# HZSneckV1_2.net
KiCad netlist of a schematic drawn in Altium Designer
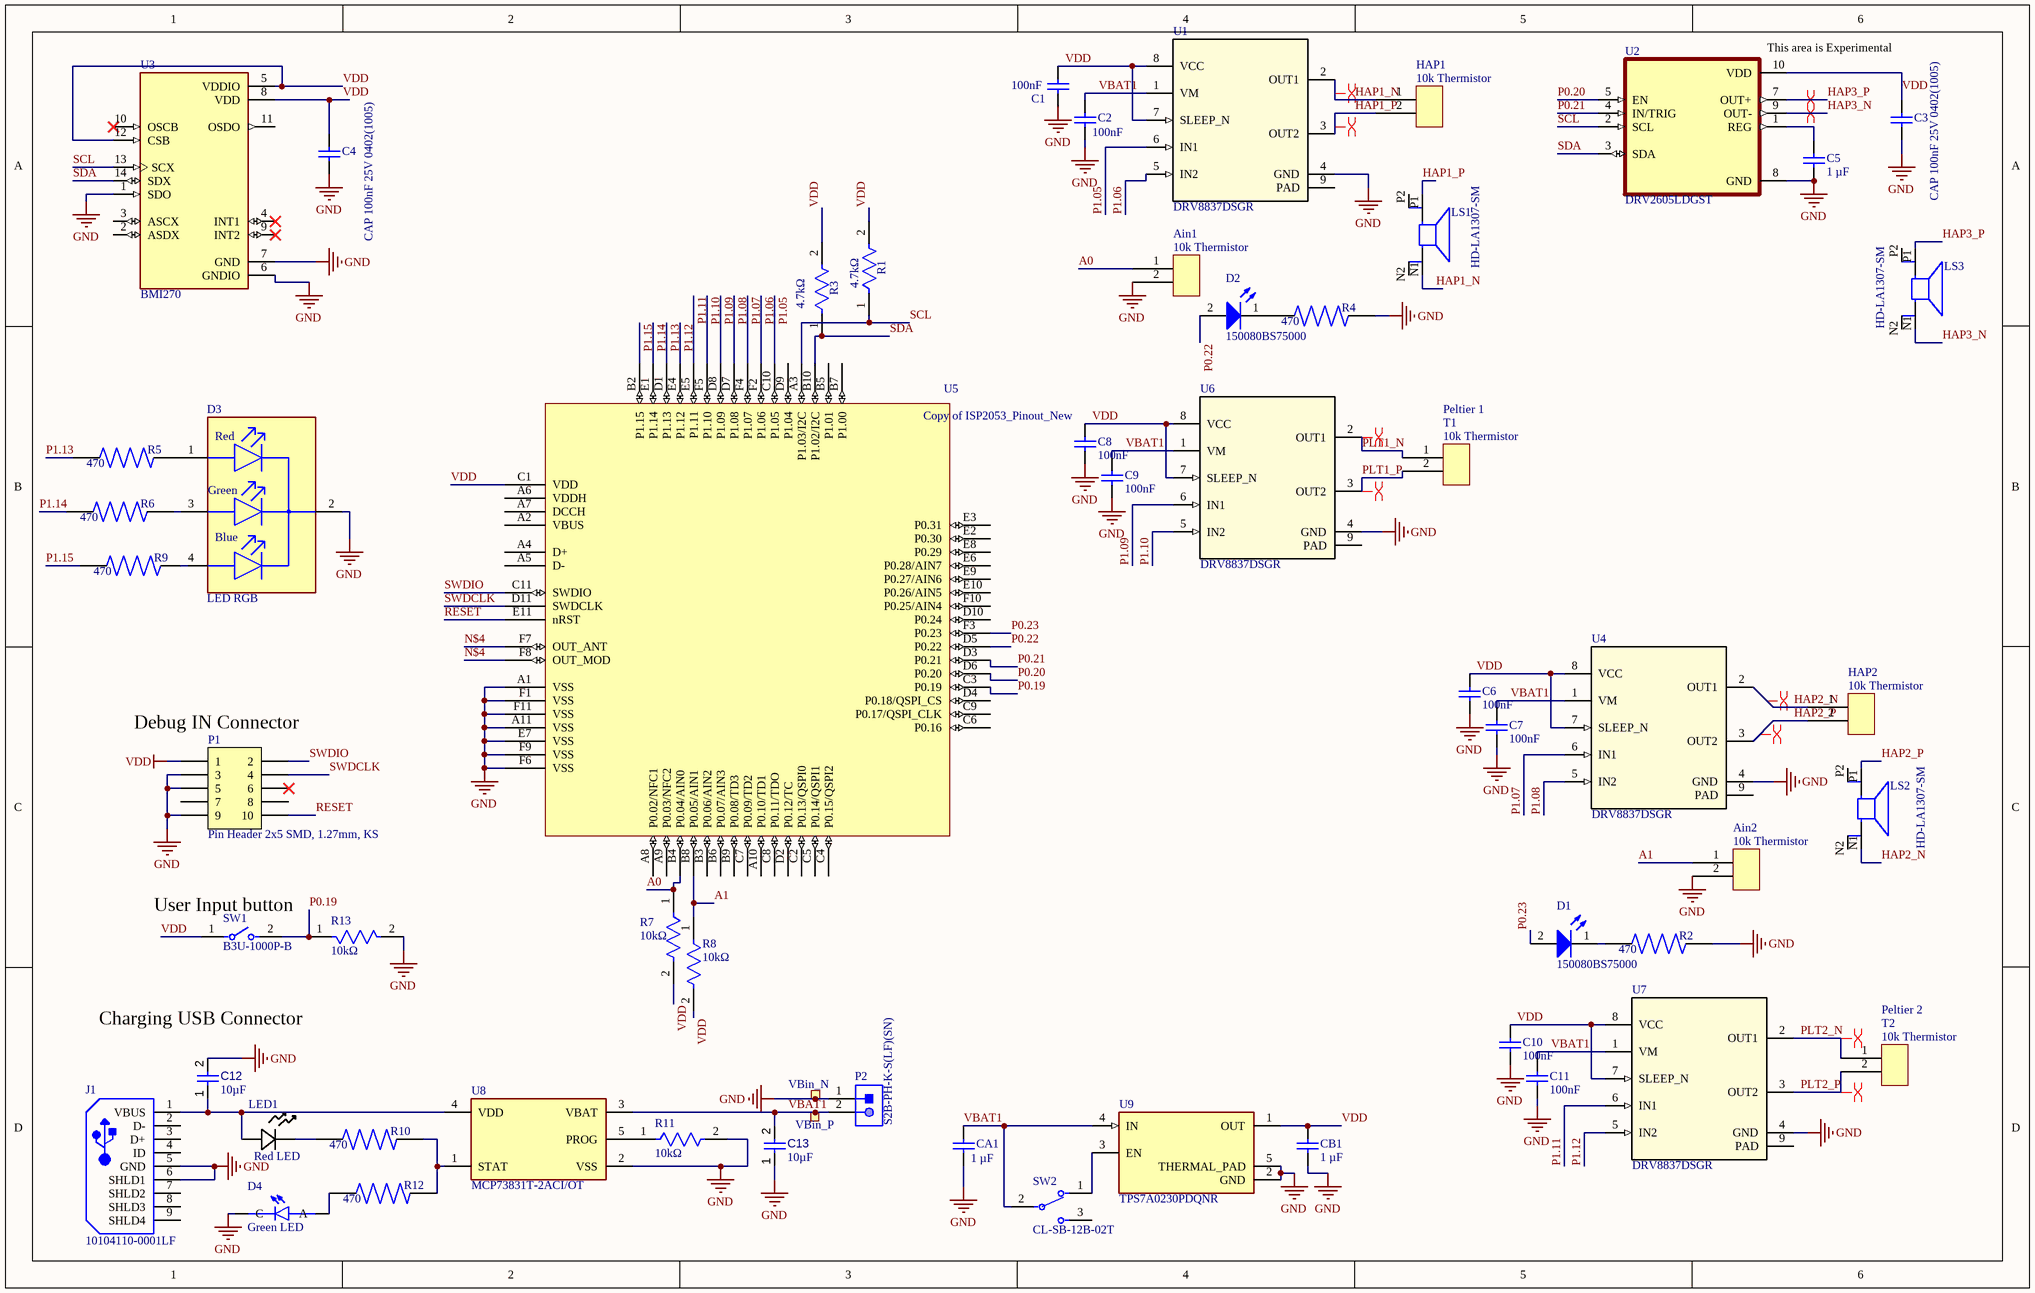
[diagram p0: HZSneckV1.2.SchDoc]

(export (version "E")
  (design (tool "Eeschema 10.0.6"))
  (components
    (comp (ref "Ain1")
      (value "10k Thermistor Custom")
      (footprint "10k Thermistor Pad")
      (description "Custom Pad for the Thermistor")
      (libsource (lib "Georgia Institute of Technology") (part "HPcustomPad-10k Thermistor"))
    )
    (comp (ref "Ain2")
      (value "10k Thermistor Custom")
      (footprint "10k Thermistor Pad")
      (description "Custom Pad for the Thermistor")
      (libsource (lib "Georgia Institute of Technology") (part "HPcustomPad-10k Thermistor"))
    )
    (comp (ref "C1")
      (value "100nF")
      (footprint "CAPC0402(1005)60_L")
      (description "CAP 100nF 25V ±20% 0402 (1005 Metric) Thickness 0.6mm SMD")
      (fields (field (name "TOLERANCE") "Â±20%"))
      (libsource (lib "Altium Content Vault") (part "CAP"))
    )
    (comp (ref "C2")
      (value "100nF")
      (footprint "CAPC0402(1005)60_L")
      (description "CAP 100nF 25V ±20% 0402 (1005 Metric) Thickness 0.6mm SMD")
      (fields (field (name "TOLERANCE") "Â±20%"))
      (libsource (lib "Altium Content Vault") (part "CAP"))
    )
    (comp (ref "C3")
      (value "CAP 100nF 25V 0402(1005)")
      (footprint "CAPC0402(1005)60_L")
      (description "CAP 100nF 25V ±20% 0402 (1005 Metric) Thickness 0.6mm SMD")
      (fields (field (name "TOLERANCE") "Â±20%"))
      (libsource (lib "Altium Content Vault") (part "CAP"))
    )
    (comp (ref "C4")
      (value "CAP 100nF 25V 0402(1005)")
      (footprint "CAPC0402(1005)60_L")
      (description "CAP 100nF 25V ±20% 0402 (1005 Metric) Thickness 0.6mm SMD")
      (fields (field (name "TOLERANCE") "Â±20%"))
      (libsource (lib "Altium Content Vault") (part "CAP"))
    )
    (comp (ref "C5")
      (value "1 µF")
      (footprint "CAPC1005X56X25ML10T15")
      (description "1 µF ±10% 6.3V Ceramic Capacitor X5R 0402 (1005 Metric)\r\n04026D105KAT4A")
      (fields
        (field (name "PART NUMBER") "04026D105KAT4A")
        (field (name "MANUFACTURER") "AVX Interconnect / Elco")
      )
      (libsource (lib "Altium Content Vault") (part "CAP"))
    )
    (comp (ref "C6")
      (value "100nF")
      (footprint "CAPC0402(1005)60_L")
      (description "CAP 100nF 25V ±20% 0402 (1005 Metric) Thickness 0.6mm SMD")
      (fields (field (name "TOLERANCE") "Â±20%"))
      (libsource (lib "Altium Content Vault") (part "CAP"))
    )
    (comp (ref "C7")
      (value "100nF")
      (footprint "CAPC0402(1005)60_L")
      (description "CAP 100nF 25V ±20% 0402 (1005 Metric) Thickness 0.6mm SMD")
      (fields (field (name "TOLERANCE") "Â±20%"))
      (libsource (lib "Altium Content Vault") (part "CAP"))
    )
    (comp (ref "C8")
      (value "100nF")
      (footprint "CAPC0402(1005)60_L")
      (description "CAP 100nF 25V ±20% 0402 (1005 Metric) Thickness 0.6mm SMD")
      (fields (field (name "TOLERANCE") "Â±20%"))
      (libsource (lib "Altium Content Vault") (part "CAP"))
    )
    (comp (ref "C9")
      (value "100nF")
      (footprint "CAPC0402(1005)60_L")
      (description "CAP 100nF 25V ±20% 0402 (1005 Metric) Thickness 0.6mm SMD")
      (fields (field (name "TOLERANCE") "Â±20%"))
      (libsource (lib "Altium Content Vault") (part "CAP"))
    )
    (comp (ref "C10")
      (value "100nF")
      (footprint "CAPC0402(1005)60_L")
      (description "CAP 100nF 25V ±20% 0402 (1005 Metric) Thickness 0.6mm SMD")
      (fields (field (name "TOLERANCE") "Â±20%"))
      (libsource (lib "Altium Content Vault") (part "CAP"))
    )
    (comp (ref "C11")
      (value "100nF")
      (footprint "CAPC0402(1005)60_L")
      (description "CAP 100nF 25V ±20% 0402 (1005 Metric) Thickness 0.6mm SMD")
      (fields (field (name "TOLERANCE") "Â±20%"))
      (libsource (lib "Altium Content Vault") (part "CAP"))
    )
    (comp (ref "C12")
      (value "10µF")
      (footprint "CAPC0402(1005)60_L")
      (description "Chip Capacitor, 10µF +/-40%, 6.3V, 0402, Thickness 0.6 mm")
      (fields (field (name "TOLERANCE") "10%") (field (name "Comment") "Capacitor 10µF +/-40% 6.3V 0402"))
      (libsource (lib "Georgia Institute of Technology") (part "CAP-NP-2"))
    )
    (comp (ref "C13")
      (value "10µF")
      (footprint "CAPC0402(1005)60_L")
      (description "Chip Capacitor, 10µF +/-40%, 6.3V, 0402, Thickness 0.6 mm")
      (fields (field (name "TOLERANCE") "10%") (field (name "Comment") "Capacitor 10µF +/-40% 6.3V 0402"))
      (libsource (lib "Georgia Institute of Technology") (part "CAP-NP-2"))
    )
    (comp (ref "CA1")
      (value "1 µF")
      (footprint "CAPC1005X56X25ML10T15")
      (description "1 µF ±10% 6.3V Ceramic Capacitor X5R 0402 (1005 Metric)\r\n04026D105KAT4A")
      (fields
        (field (name "PART NUMBER") "04026D105KAT4A")
        (field (name "MANUFACTURER") "AVX Interconnect / Elco")
      )
      (libsource (lib "Altium Content Vault") (part "CAP"))
    )
    (comp (ref "CB1")
      (value "1 µF")
      (footprint "CAPC1005X56X25ML10T15")
      (description "1 µF ±10% 6.3V Ceramic Capacitor X5R 0402 (1005 Metric)\r\n04026D105KAT4A")
      (fields
        (field (name "PART NUMBER") "04026D105KAT4A")
        (field (name "MANUFACTURER") "AVX Interconnect / Elco")
      )
      (libsource (lib "Altium Content Vault") (part "CAP"))
    )
    (comp (ref "D1")
      (value "150080BS75000")
      (footprint "WL-SMCW_0805_150080xx75000")
      (description "Led, Blue, 470 Nm, 3.2 V, 30 Ma, 145 Mcd Rohs Compliant: Yes")
      (libsource (lib "Altium Content Vault") (part "LED_Blue_2A-1K"))
    )
    (comp (ref "D2")
      (value "150080BS75000")
      (footprint "WL-SMCW_0805_150080xx75000")
      (description "Led, Blue, 470 Nm, 3.2 V, 30 Ma, 145 Mcd Rohs Compliant: Yes")
      (libsource (lib "Altium Content Vault") (part "LED_Blue_2A-1K"))
    )
    (comp (ref "D3")
      (value "LED RGB")
      (footprint "FP-AAA3528LSEKJ3ZGKQBKS-MFG")
      (description "LED RGB CLEAR 4SMD\r\nAAA3528LSEKJ3ZGKQBKS")
      (libsource (lib "Altium Content Vault") (part "443e5383a7a0c9f1439af3e1184479d"))
    )
    (comp (ref "D4")
      (value "Green LED")
      (footprint "LEDC2012X120N")
      (description "Green LED, 565 nm 0805Diffused, Rectangle Lens SMD package\r\nSML-LXT0805GW-TR")
      (fields (field (name "MF") "Lumex Opto/Components") (field (name "MP") "SML-LXT0805GW-TR"))
      (libsource (lib "Georgia Institute of Technology") (part "SML-LXT0805GW-TR"))
    )
    (comp (ref "HAP1")
      (value "10k Thermistor Custom")
      (footprint "10k Thermistor Pad")
      (description "Custom Pad for the Thermistor")
      (libsource (lib "Georgia Institute of Technology") (part "HPcustomPad-10k Thermistor"))
    )
    (comp (ref "HAP2")
      (value "10k Thermistor Custom")
      (footprint "10k Thermistor Pad")
      (description "Custom Pad for the Thermistor")
      (libsource (lib "Georgia Institute of Technology") (part "HPcustomPad-10k Thermistor"))
    )
    (comp (ref "J1")
      (value "10104110-0001LF")
      (footprint "FCI-10104110-0001LF_V")
      (description "Micro USB, Receptacle, -55 to 85 degC, 5-Pin SMD, RoHS, Tape and Reel")
      (fields (field (name "MANUFACTURER") "FCI Electronics"))
      (libsource (lib "Altium Content Vault") (part "USB-5-4SHLD"))
    )
    (comp (ref "LED1")
      (value "Red LED")
      (footprint "LED_LS R976_AOS")
      (description "LS R976-NR-1")
      (fields (field (name "COPYRIGHT") "Copyright (C) 2025 Ultra Librarian. All rights reserved."))
      (libsource (lib "Georgia Institute of Technology") (part "LS R976-NR-1"))
    )
    (comp (ref "LS1")
      (value "HD-LA1307-SM")
      (footprint "XDCR_HD-LA1307-SM")
      (description "13X13MM LRA HAPTIC 154HZ")
      (fields (field (name "MF") "PUI Audio, Inc."))
      (libsource (lib "Georgia Institute of Technology") (part "HD-LA1307-SM"))
    )
    (comp (ref "LS2")
      (value "HD-LA1307-SM")
      (footprint "XDCR_HD-LA1307-SM")
      (description "13X13MM LRA HAPTIC 154HZ")
      (fields (field (name "MF") "PUI Audio, Inc."))
      (libsource (lib "Georgia Institute of Technology") (part "HD-LA1307-SM"))
    )
    (comp (ref "LS3")
      (value "HD-LA1307-SM")
      (footprint "XDCR_HD-LA1307-SM")
      (description "13X13MM LRA HAPTIC 154HZ")
      (fields (field (name "MF") "PUI Audio, Inc."))
      (libsource (lib "Georgia Institute of Technology") (part "HD-LA1307-SM"))
    )
    (comp (ref "P1")
      (value "Pin Header 2x5 SMD, 1.27mm, KS")
      (footprint "HDR_2x5-SMD-1.27mm-K")
      (description "Pin Header 2x5, 1.27mm (50mil), SMD, Keying Shroud")
      (fields
        (field (name "MANUFACTURER PART NUMBER") "3132-10MS0BK00R1")
        (field (name "MANUFACTURER") "W-CON")
        (field (name "PUBLISHER") "Nordic Semiconductor")
      )
      (libsource (lib "Georgia Institute of Technology") (part "Pin Header 2x5 SMD, 1.27mm, KS"))
    )
    (comp (ref "P2")
      (value "S2B-PH-K-S(LF)(SN)")
      (footprint "JST-S2B-PH-K-S_V")
      (fields (field (name "TOLERANCE") "20%"))
      (libsource (lib "Altium Content Vault") (part "CN-1P-M-R2"))
    )
    (comp (ref "R1")
      (value "4.7kΩ")
      (footprint "FP-TFCR0603-MFG")
      (description "RES Thin Film,  4.7kΩ, 1%, 0.1W, 50ppm/°C, 0603TFCR0603-10W-C-4701FT-1K")
      (libsource (lib "Altium Content Vault") (part "1029c3af85768c4190bb7ad29bc67b5"))
    )
    (comp (ref "R2")
      (value "470")
      (footprint "RESC1608X55N")
      (description "RESISTOR, SURGE, 470 OHM 1% 0603")
      (fields (field (name "MP") "SG73P1JTTD4700F"))
      (libsource (lib "Georgia Institute of Technology") (part "SG73P1JTTD4700F"))
    )
    (comp (ref "R3")
      (value "4.7kΩ")
      (footprint "FP-TFCR0603-MFG")
      (description "RES Thin Film,  4.7kΩ, 1%, 0.1W, 50ppm/°C, 0603TFCR0603-10W-C-4701FT-1K")
      (libsource (lib "Altium Content Vault") (part "1029c3af85768c4190bb7ad29bc67b5"))
    )
    (comp (ref "R4")
      (value "470")
      (footprint "RESC1608X55N")
      (description "RESISTOR, SURGE, 470 OHM 1% 0603")
      (fields (field (name "MP") "SG73P1JTTD4700F"))
      (libsource (lib "Georgia Institute of Technology") (part "SG73P1JTTD4700F"))
    )
    (comp (ref "R5")
      (value "470")
      (footprint "RESC1608X55N")
      (description "RESISTOR, SURGE, 470 OHM 1% 0603")
      (fields (field (name "MP") "SG73P1JTTD4700F"))
      (libsource (lib "Georgia Institute of Technology") (part "SG73P1JTTD4700F"))
    )
    (comp (ref "R6")
      (value "470")
      (footprint "RESC1608X55N")
      (description "RESISTOR, SURGE, 470 OHM 1% 0603")
      (fields (field (name "MP") "SG73P1JTTD4700F"))
      (libsource (lib "Georgia Institute of Technology") (part "SG73P1JTTD4700F"))
    )
    (comp (ref "R7")
      (value "10kΩ")
      (footprint "FP-AC0603-IPC_A")
      (description "RES 10kΩ 5.00% 0.2W 0603\r\nAC0603JR-7W10KL")
      (libsource (lib "Altium Content Vault") (part "1029c3af85768c4190bb7ad29bc67b5"))
    )
    (comp (ref "R8")
      (value "10kΩ")
      (footprint "FP-AC0603-IPC_A")
      (description "RES 10kΩ 5.00% 0.2W 0603\r\nAC0603JR-7W10KL")
      (libsource (lib "Altium Content Vault") (part "1029c3af85768c4190bb7ad29bc67b5"))
    )
    (comp (ref "R9")
      (value "470")
      (footprint "RESC1608X55N")
      (description "RESISTOR, SURGE, 470 OHM 1% 0603")
      (fields (field (name "MP") "SG73P1JTTD4700F"))
      (libsource (lib "Georgia Institute of Technology") (part "SG73P1JTTD4700F"))
    )
    (comp (ref "R10")
      (value "470")
      (footprint "RESC1608X55N")
      (description "RESISTOR, SURGE, 470 OHM 1% 0603")
      (fields (field (name "MP") "SG73P1JTTD4700F"))
      (libsource (lib "Georgia Institute of Technology") (part "SG73P1JTTD4700F"))
    )
    (comp (ref "R11")
      (value "10kΩ")
      (footprint "FP-AC0603-IPC_A")
      (description "RES 10kΩ 5.00% 0.2W 0603\r\nAC0603JR-7W10KL")
      (libsource (lib "Altium Content Vault") (part "1029c3af85768c4190bb7ad29bc67b5"))
    )
    (comp (ref "R12")
      (value "470")
      (footprint "RESC1608X55N")
      (description "RESISTOR, SURGE, 470 OHM 1% 0603")
      (fields (field (name "MP") "SG73P1JTTD4700F"))
      (libsource (lib "Georgia Institute of Technology") (part "SG73P1JTTD4700F"))
    )
    (comp (ref "R13")
      (value "10kΩ")
      (footprint "FP-AC0603-IPC_A")
      (description "RES 10kΩ 5.00% 0.2W 0603\r\nAC0603JR-7W10KL")
      (libsource (lib "Altium Content Vault") (part "1029c3af85768c4190bb7ad29bc67b5"))
    )
    (comp (ref "SW1")
      (value "B3U-1000P-B")
      (footprint "FP-B3U-1000P-B-MFG")
      (description "SWITCH TACTILE SPST-NO 0.05A 12V")
      (fields
        (field (name "OCTOPART") "https://octopart.com/b3u-1000p-b-omron-1057356")
        (field (name "MANUFACTURER") "Omron")
      )
      (libsource (lib "Altium Content Vault") (part "bb27bde45df87f1f469753f287ef5ae"))
    )
    (comp (ref "SW2")
      (value "CL-SB-12B-02T")
      (footprint "FP-CL-SB-12B-02T-MFG")
      (description "SWITCH SLIDE SPDT 200MA 12V")
      (libsource (lib "Altium Content Vault") (part "39e195cbbadc85d1df0d7eb6847d379"))
    )
    (comp (ref "T1")
      (value "Peltier 1")
      (footprint "10k Thermistor Pad")
      (description "Custom Pad for the Thermistor")
      (libsource (lib "Georgia Institute of Technology") (part "HPcustomPad-10k Thermistor"))
    )
    (comp (ref "T2")
      (value "Peltier 2")
      (footprint "10k Thermistor Pad")
      (description "Custom Pad for the Thermistor")
      (libsource (lib "Georgia Institute of Technology") (part "HPcustomPad-10k Thermistor"))
    )
    (comp (ref "U1")
      (value "DRV8837DSGR")
      (footprint "DSG0008A")
      (description "12-V, 1.8-A H-bridge motor driver 8-WSON -40 to 85")
      (fields (field (name "COPYRIGHT") "Copyright (C) 2025 Ultra Librarian. All rights reserved."))
      (libsource (lib "Georgia Institute of Technology") (part "DRV8837DSGR"))
    )
    (comp (ref "U2")
      (value "DRV2605LDGST")
      (footprint "SOP50P490X110-10N")
      (description "Haptic driver for ERM/LRA with 2-V operation, waveform library & auto-resonance tracking")
      (fields (field (name "MF") "Texas Instruments"))
      (libsource (lib "Georgia Institute of Technology") (part "DRV2605LDGST"))
    )
    (comp (ref "U3")
      (value "BMI270")
      (footprint "XDCR_BMI270")
      (description "Accelerometer, Gyroscope, 6 Axis Sensor IÂ²C, SPI Output")
      (fields (field (name "MF") "Bosch Sensortec") (field (name "DIGI-KEY_PART_NUMBER") "828-1091-2-ND"))
      (libsource (lib "Georgia Institute of Technology") (part "BMI270"))
    )
    (comp (ref "U4")
      (value "DRV8837DSGR")
      (footprint "DSG0008A")
      (description "12-V, 1.8-A H-bridge motor driver 8-WSON -40 to 85")
      (fields (field (name "COPYRIGHT") "Copyright (C) 2025 Ultra Librarian. All rights reserved."))
      (libsource (lib "Georgia Institute of Technology") (part "DRV8837DSGR"))
    )
    (comp (ref "U5")
      (value "Copy of ISP2053_Pinout_New")
      (footprint "Copy of ISP2053-AX")
      (description "ISP Smart Bluetooth Module")
      (fields (field (name "ISP_PART") "ISP1807") (field (name "SOURCE") "ISPlibSch.SchLib"))
      (libsource (lib "Georgia Institute of Technology") (part "ISP2053_Pinout_New"))
    )
    (comp (ref "U6")
      (value "DRV8837DSGR")
      (footprint "DSG0008A")
      (description "12-V, 1.8-A H-bridge motor driver 8-WSON -40 to 85")
      (fields (field (name "COPYRIGHT") "Copyright (C) 2025 Ultra Librarian. All rights reserved."))
      (libsource (lib "Georgia Institute of Technology") (part "DRV8837DSGR"))
    )
    (comp (ref "U7")
      (value "DRV8837DSGR")
      (footprint "DSG0008A")
      (description "12-V, 1.8-A H-bridge motor driver 8-WSON -40 to 85")
      (fields (field (name "COPYRIGHT") "Copyright (C) 2025 Ultra Librarian. All rights reserved."))
      (libsource (lib "Georgia Institute of Technology") (part "DRV8837DSGR"))
    )
    (comp (ref "U8")
      (value "MCP73831T-2ACI/OT")
      (footprint "FP-C04-091-OT-IPC_B")
      (description "IC CONTROLLR LI-ION 4.2V SOT23-5")
      (libsource (lib "Altium Content Vault") (part "61f5a3bb3429d9e0caadea342aa3b19"))
    )
    (comp (ref "U9")
      (value "TPS7A0230PDQNR")
      (footprint "IC_TPS7A0230PDQNR")
      (description "200-mA, nanopower-IQ (25 nA), low-dropout (LDO) voltage regulator with enable")
      (fields (field (name "MF") "Texas Instruments"))
      (libsource (lib "Georgia Institute of Technology") (part "TPS7A0230PDQNR"))
    )
    (comp (ref "VBin_N")
      (value "TP_SMD_Ø1.0MM")
      (footprint "TP_SMD_Ø1.0mm")
      (description "1.0mm circular SMD testpad")
      (fields
        (field (name "MANUFACTURER") "Nordic Semiconductor")
        (field (name "MANUFACTURER PART NUMBER") "N.A.")
        (field (name "PUBLISHER") "Nordic Semiconductor")
      )
      (libsource (lib "") (part "TP_SMD_Ø1.5MM_1"))
    )
    (comp (ref "VBin_P")
      (value "TP_SMD_Ø1.0MM")
      (footprint "TP_SMD_Ø1.0mm")
      (description "1.0mm circular SMD testpad")
      (fields
        (field (name "MANUFACTURER") "Nordic Semiconductor")
        (field (name "MANUFACTURER PART NUMBER") "N.A.")
        (field (name "PUBLISHER") "Nordic Semiconductor")
      )
      (libsource (lib "Georgia Institute of Technology") (part "TP_SMD_Ø1.5MM"))
    )
  )
  (nets
    (net (code "2") (name "/A0") (class "Default")
      (node (ref "Ain1") (pin "1") (pintype "passive"))
      (node (ref "R7") (pin "1") (pinfunction "1_1") (pintype "passive"))
      (node (ref "U5") (pin "B4") (pinfunction "P0.04/AIN0_B4") (pintype "bidirectional"))
    )
    (net (code "3") (name "/A1") (class "Default")
      (node (ref "Ain2") (pin "1") (pintype "passive"))
      (node (ref "R8") (pin "1") (pinfunction "1_1") (pintype "passive"))
      (node (ref "U5") (pin "B8") (pinfunction "P0.05/AIN1_B8") (pintype "bidirectional"))
    )
    (net (code "4") (name "/HAP1_N") (class "Default")
      (node (ref "HAP1") (pin "1") (pintype "passive"))
      (node (ref "LS1") (pin "N1") (pinfunction "N1_N1") (pintype "passive"))
      (node (ref "U1") (pin "2") (pinfunction "OUT1_2") (pintype "power_in"))
    )
    (net (code "5") (name "/HAP1_P") (class "Default")
      (node (ref "HAP1") (pin "2") (pintype "passive"))
      (node (ref "LS1") (pin "P1") (pinfunction "P1_P1") (pintype "passive"))
      (node (ref "U1") (pin "3") (pinfunction "OUT2_3") (pintype "power_in"))
    )
    (net (code "6") (name "/HAP2_N") (class "Default")
      (node (ref "HAP2") (pin "1") (pintype "passive"))
      (node (ref "LS2") (pin "N1") (pinfunction "N1_N1") (pintype "passive"))
      (node (ref "U4") (pin "2") (pinfunction "OUT1_2") (pintype "power_in"))
    )
    (net (code "7") (name "/HAP2_P") (class "Default")
      (node (ref "HAP2") (pin "2") (pintype "passive"))
      (node (ref "LS2") (pin "P1") (pinfunction "P1_P1") (pintype "passive"))
      (node (ref "U4") (pin "3") (pinfunction "OUT2_3") (pintype "power_in"))
    )
    (net (code "8") (name "/HAP3_N") (class "Default")
      (node (ref "LS3") (pin "N1") (pinfunction "N1_N1") (pintype "passive"))
      (node (ref "U2") (pin "9") (pinfunction "OUT-_9") (pintype "output"))
    )
    (net (code "9") (name "/HAP3_P") (class "Default")
      (node (ref "LS3") (pin "P1") (pinfunction "P1_P1") (pintype "passive"))
      (node (ref "U2") (pin "7") (pinfunction "OUT+_7") (pintype "output"))
    )
    (net (code "10") (name "/N$4") (class "Default")
      (node (ref "U5") (pin "F7") (pinfunction "OUT_ANT_F7") (pintype "bidirectional"))
      (node (ref "U5") (pin "F8") (pinfunction "OUT_MOD_F8") (pintype "bidirectional"))
    )
    (net (code "11") (name "/P0.19") (class "Default")
      (node (ref "R13") (pin "1") (pinfunction "1_1") (pintype "passive"))
      (node (ref "SW1") (pin "2") (pinfunction "2_2") (pintype "passive"))
      (node (ref "U5") (pin "C3") (pinfunction "P0.19_C3") (pintype "bidirectional"))
    )
    (net (code "12") (name "/P0.20") (class "Default")
      (node (ref "U2") (pin "5") (pinfunction "EN_5") (pintype "input"))
      (node (ref "U5") (pin "D6") (pinfunction "P0.20_D6") (pintype "bidirectional"))
    )
    (net (code "13") (name "/P0.21") (class "Default")
      (node (ref "U2") (pin "4") (pinfunction "IN/TRIG_4") (pintype "input"))
      (node (ref "U5") (pin "D3") (pinfunction "P0.21_D3") (pintype "bidirectional"))
    )
    (net (code "14") (name "/P0.22") (class "Default")
      (node (ref "D2") (pin "2") (pinfunction "A_2") (pintype "passive"))
      (node (ref "U5") (pin "D5") (pinfunction "P0.22_D5") (pintype "bidirectional"))
    )
    (net (code "15") (name "/P0.23") (class "Default")
      (node (ref "D1") (pin "2") (pinfunction "A_2") (pintype "passive"))
      (node (ref "U5") (pin "F3") (pinfunction "P0.23_F3") (pintype "bidirectional"))
    )
    (net (code "16") (name "/P1.05") (class "Default")
      (node (ref "U1") (pin "6") (pinfunction "IN1_6") (pintype "input"))
      (node (ref "U5") (pin "C10") (pinfunction "P1.05_C10") (pintype "bidirectional"))
    )
    (net (code "17") (name "/P1.06") (class "Default")
      (node (ref "U1") (pin "5") (pinfunction "IN2_5") (pintype "input"))
      (node (ref "U5") (pin "F2") (pinfunction "P1.06_F2") (pintype "bidirectional"))
    )
    (net (code "18") (name "/P1.07") (class "Default")
      (node (ref "U4") (pin "6") (pinfunction "IN1_6") (pintype "input"))
      (node (ref "U5") (pin "F4") (pinfunction "P1.07_F4") (pintype "bidirectional"))
    )
    (net (code "19") (name "/P1.08") (class "Default")
      (node (ref "U4") (pin "5") (pinfunction "IN2_5") (pintype "input"))
      (node (ref "U5") (pin "D7") (pinfunction "P1.08_D7") (pintype "bidirectional"))
    )
    (net (code "20") (name "/P1.09") (class "Default")
      (node (ref "U5") (pin "D8") (pinfunction "P1.09_D8") (pintype "bidirectional"))
      (node (ref "U6") (pin "6") (pinfunction "IN1_6") (pintype "input"))
    )
    (net (code "21") (name "/P1.10") (class "Default")
      (node (ref "U5") (pin "F5") (pinfunction "P1.10_F5") (pintype "bidirectional"))
      (node (ref "U6") (pin "5") (pinfunction "IN2_5") (pintype "input"))
    )
    (net (code "22") (name "/P1.11") (class "Default")
      (node (ref "U5") (pin "E5") (pinfunction "P1.11_E5") (pintype "bidirectional"))
      (node (ref "U7") (pin "6") (pinfunction "IN1_6") (pintype "input"))
    )
    (net (code "23") (name "/P1.12") (class "Default")
      (node (ref "U5") (pin "E4") (pinfunction "P1.12_E4") (pintype "bidirectional"))
      (node (ref "U7") (pin "5") (pinfunction "IN2_5") (pintype "input"))
    )
    (net (code "24") (name "/P1.13") (class "Default")
      (node (ref "R5") (pin "1") (pinfunction "1_1") (pintype "passive"))
      (node (ref "U5") (pin "D1") (pinfunction "P1.13_D1") (pintype "bidirectional"))
    )
    (net (code "25") (name "/P1.14") (class "Default")
      (node (ref "R6") (pin "1") (pinfunction "1_1") (pintype "passive"))
      (node (ref "U5") (pin "E1") (pinfunction "P1.14_E1") (pintype "bidirectional"))
    )
    (net (code "26") (name "/P1.15") (class "Default")
      (node (ref "R9") (pin "1") (pinfunction "1_1") (pintype "passive"))
      (node (ref "U5") (pin "B2") (pinfunction "P1.15_B2") (pintype "bidirectional"))
    )
    (net (code "27") (name "/PLT1_N") (class "Default")
      (node (ref "T1") (pin "1") (pintype "passive"))
      (node (ref "U6") (pin "2") (pinfunction "OUT1_2") (pintype "power_in"))
    )
    (net (code "28") (name "/PLT1_P") (class "Default")
      (node (ref "T1") (pin "2") (pintype "passive"))
      (node (ref "U6") (pin "3") (pinfunction "OUT2_3") (pintype "power_in"))
    )
    (net (code "29") (name "/PLT2_N") (class "Default")
      (node (ref "T2") (pin "1") (pintype "passive"))
      (node (ref "U7") (pin "2") (pinfunction "OUT1_2") (pintype "power_in"))
    )
    (net (code "30") (name "/PLT2_P") (class "Default")
      (node (ref "T2") (pin "2") (pintype "passive"))
      (node (ref "U7") (pin "3") (pinfunction "OUT2_3") (pintype "power_in"))
    )
    (net (code "31") (name "/RESET") (class "Default")
      (node (ref "P1") (pin "10") (pinfunction "10_10") (pintype "passive"))
      (node (ref "U5") (pin "E11") (pinfunction "nRST_E11") (pintype "power_in"))
    )
    (net (code "32") (name "/SCL") (class "Default")
      (node (ref "R1") (pin "1") (pinfunction "1_1") (pintype "passive"))
      (node (ref "U2") (pin "2") (pinfunction "SCL_2") (pintype "input"))
      (node (ref "U3") (pin "13") (pinfunction "SCX_13") (pintype "input"))
      (node (ref "U5") (pin "A3") (pinfunction "P1.03/I2C_A3") (pintype "bidirectional"))
    )
    (net (code "33") (name "/SDA") (class "Default")
      (node (ref "R3") (pin "1") (pinfunction "1_1") (pintype "passive"))
      (node (ref "U2") (pin "3") (pinfunction "SDA_3") (pintype "bidirectional"))
      (node (ref "U3") (pin "14") (pinfunction "SDX_14") (pintype "bidirectional"))
      (node (ref "U5") (pin "B10") (pinfunction "P1.02/I2C_B10") (pintype "bidirectional"))
    )
    (net (code "34") (name "/SWDCLK") (class "Default")
      (node (ref "P1") (pin "4") (pinfunction "4_4") (pintype "passive"))
      (node (ref "U5") (pin "D11") (pinfunction "SWDCLK_D11") (pintype "passive"))
    )
    (net (code "35") (name "/SWDIO") (class "Default")
      (node (ref "P1") (pin "2") (pinfunction "2_2") (pintype "passive"))
      (node (ref "U5") (pin "C11") (pinfunction "SWDIO_C11") (pintype "bidirectional"))
    )
    (net (code "36") (name "/VBAT1") (class "Default")
      (node (ref "C11") (pin "2") (pinfunction "2_2") (pintype "passive"))
      (node (ref "C13") (pin "2") (pinfunction "2_2") (pintype "passive"))
      (node (ref "C2") (pin "2") (pinfunction "2_2") (pintype "passive"))
      (node (ref "C7") (pin "2") (pinfunction "2_2") (pintype "passive"))
      (node (ref "C9") (pin "2") (pinfunction "2_2") (pintype "passive"))
      (node (ref "CA1") (pin "2") (pinfunction "2_2") (pintype "passive"))
      (node (ref "P2") (pin "2") (pinfunction "2_2") (pintype "passive"))
      (node (ref "SW2") (pin "2") (pinfunction "C_2") (pintype "passive"))
      (node (ref "U1") (pin "1") (pinfunction "VM_1") (pintype "power_in"))
      (node (ref "U4") (pin "1") (pinfunction "VM_1") (pintype "power_in"))
      (node (ref "U6") (pin "1") (pinfunction "VM_1") (pintype "power_in"))
      (node (ref "U7") (pin "1") (pinfunction "VM_1") (pintype "power_in"))
      (node (ref "U8") (pin "3") (pinfunction "VBAT_3") (pintype "power_in"))
      (node (ref "U9") (pin "4") (pinfunction "IN_4") (pintype "input"))
      (node (ref "VBin_P") (pin "1") (pinfunction "1_1") (pintype "passive"))
    )
    (net (code "37") (name "GND") (class "Default")
      (node (ref "Ain1") (pin "2") (pintype "passive"))
      (node (ref "Ain2") (pin "2") (pintype "passive"))
      (node (ref "C1") (pin "1") (pinfunction "1_1") (pintype "passive"))
      (node (ref "C10") (pin "1") (pinfunction "1_1") (pintype "passive"))
      (node (ref "C11") (pin "1") (pinfunction "1_1") (pintype "passive"))
      (node (ref "C12") (pin "2") (pinfunction "2_2") (pintype "passive"))
      (node (ref "C13") (pin "1") (pinfunction "1_1") (pintype "passive"))
      (node (ref "C2") (pin "1") (pinfunction "1_1") (pintype "passive"))
      (node (ref "C3") (pin "1") (pinfunction "1_1") (pintype "passive"))
      (node (ref "C4") (pin "1") (pinfunction "1_1") (pintype "passive"))
      (node (ref "C5") (pin "1") (pinfunction "1_1") (pintype "passive"))
      (node (ref "C6") (pin "1") (pinfunction "1_1") (pintype "passive"))
      (node (ref "C7") (pin "1") (pinfunction "1_1") (pintype "passive"))
      (node (ref "C8") (pin "1") (pinfunction "1_1") (pintype "passive"))
      (node (ref "C9") (pin "1") (pinfunction "1_1") (pintype "passive"))
      (node (ref "CA1") (pin "1") (pinfunction "1_1") (pintype "passive"))
      (node (ref "CB1") (pin "1") (pinfunction "1_1") (pintype "passive"))
      (node (ref "D3") (pin "2") (pinfunction "COMMON_CATHODE_2") (pintype "passive"))
      (node (ref "D4") (pin "C") (pinfunction "C_C") (pintype "passive"))
      (node (ref "J1") (pin "5") (pinfunction "GND_5") (pintype "power_in"))
      (node (ref "J1") (pin "6") (pinfunction "SHLD1_6") (pintype "passive"))
      (node (ref "P1") (pin "3") (pinfunction "3_3") (pintype "passive"))
      (node (ref "P1") (pin "5") (pinfunction "5_5") (pintype "passive"))
      (node (ref "P1") (pin "9") (pinfunction "9_9") (pintype "passive"))
      (node (ref "P2") (pin "1") (pinfunction "1_1") (pintype "passive"))
      (node (ref "R11") (pin "2") (pinfunction "2_2") (pintype "passive"))
      (node (ref "R13") (pin "2") (pinfunction "2_2") (pintype "passive"))
      (node (ref "R2") (pin "2") (pinfunction "2_2") (pintype "passive"))
      (node (ref "R4") (pin "2") (pinfunction "2_2") (pintype "passive"))
      (node (ref "U1") (pin "4") (pinfunction "GND_4") (pintype "power_in"))
      (node (ref "U2") (pin "8") (pinfunction "GND_8") (pintype "power_in"))
      (node (ref "U3") (pin "1") (pinfunction "SDO_1") (pintype "input"))
      (node (ref "U3") (pin "6") (pinfunction "GNDIO_6") (pintype "power_in"))
      (node (ref "U3") (pin "7") (pinfunction "GND_7") (pintype "power_in"))
      (node (ref "U4") (pin "4") (pinfunction "GND_4") (pintype "power_in"))
      (node (ref "U5") (pin "A1") (pinfunction "VSS_A1") (pintype "power_in"))
      (node (ref "U5") (pin "A11") (pinfunction "VSS_A11") (pintype "power_in"))
      (node (ref "U5") (pin "E7") (pinfunction "VSS_E7") (pintype "power_in"))
      (node (ref "U5") (pin "F1") (pinfunction "VSS_F1") (pintype "power_in"))
      (node (ref "U5") (pin "F11") (pinfunction "VSS_F11") (pintype "power_in"))
      (node (ref "U5") (pin "F6") (pinfunction "VSS_F6") (pintype "power_in"))
      (node (ref "U5") (pin "F9") (pinfunction "VSS_F9") (pintype "power_in"))
      (node (ref "U6") (pin "4") (pinfunction "GND_4") (pintype "power_in"))
      (node (ref "U7") (pin "4") (pinfunction "GND_4") (pintype "power_in"))
      (node (ref "U8") (pin "2") (pinfunction "VSS_2") (pintype "power_in"))
      (node (ref "U9") (pin "2") (pinfunction "GND_2") (pintype "power_in"))
      (node (ref "U9") (pin "5") (pinfunction "THERMAL_PAD_5") (pintype "power_in"))
      (node (ref "VBin_N") (pin "1") (pinfunction "1_1") (pintype "passive"))
    )
    (net (code "38") (name "Net-(D1-K)") (class "Default")
      (node (ref "D1") (pin "1") (pinfunction "K_1") (pintype "passive"))
      (node (ref "R2") (pin "1") (pinfunction "1_1") (pintype "passive"))
    )
    (net (code "39") (name "Net-(D2-K)") (class "Default")
      (node (ref "D2") (pin "1") (pinfunction "K_1") (pintype "passive"))
      (node (ref "R4") (pin "1") (pinfunction "1_1") (pintype "passive"))
    )
    (net (code "40") (name "Net-(D3-ANODE_BLUE)") (class "Default")
      (node (ref "D3") (pin "4") (pinfunction "ANODE_BLUE_4") (pintype "passive"))
      (node (ref "R9") (pin "2") (pinfunction "2_2") (pintype "passive"))
    )
    (net (code "41") (name "Net-(D3-ANODE_GREEN)") (class "Default")
      (node (ref "D3") (pin "3") (pinfunction "ANODE_GREEN_3") (pintype "passive"))
      (node (ref "R6") (pin "2") (pinfunction "2_2") (pintype "passive"))
    )
    (net (code "42") (name "Net-(D3-ANODE_RED)") (class "Default")
      (node (ref "D3") (pin "1") (pinfunction "ANODE_RED_1") (pintype "passive"))
      (node (ref "R5") (pin "2") (pinfunction "2_2") (pintype "passive"))
    )
    (net (code "43") (name "Net-(D4-PadA)") (class "Default")
      (node (ref "D4") (pin "A") (pinfunction "A_A") (pintype "passive"))
      (node (ref "R12") (pin "1") (pinfunction "1_1") (pintype "passive"))
    )
    (net (code "44") (name "Net-(J1-VBUS)") (class "Default")
      (node (ref "C12") (pin "1") (pinfunction "1_1") (pintype "passive"))
      (node (ref "J1") (pin "1") (pinfunction "VBUS_1") (pintype "power_in"))
      (node (ref "LED1") (pin "2") (pinfunction "2_2") (pintype "passive"))
      (node (ref "U8") (pin "4") (pinfunction "VDD_4") (pintype "power_in"))
    )
    (net (code "45") (name "Net-(LED1-Pad1)") (class "Default")
      (node (ref "LED1") (pin "1") (pinfunction "1_1") (pintype "passive"))
      (node (ref "R10") (pin "1") (pinfunction "1_1") (pintype "passive"))
    )
    (net (code "46") (name "Net-(U2-REG)") (class "Default")
      (node (ref "C5") (pin "2") (pinfunction "2_2") (pintype "passive"))
      (node (ref "U2") (pin "1") (pinfunction "REG_1") (pintype "output"))
    )
    (net (code "47") (name "Net-(U8-PROG)") (class "Default")
      (node (ref "R11") (pin "1") (pinfunction "1_1") (pintype "passive"))
      (node (ref "U8") (pin "5") (pinfunction "PROG_5") (pintype "passive"))
    )
    (net (code "48") (name "Net-(U8-STAT)") (class "Default")
      (node (ref "R10") (pin "2") (pinfunction "2_2") (pintype "passive"))
      (node (ref "R12") (pin "2") (pinfunction "2_2") (pintype "passive"))
      (node (ref "U8") (pin "1") (pinfunction "STAT_1") (pintype "passive"))
    )
    (net (code "49") (name "Net-(U9-EN)") (class "Default")
      (node (ref "SW2") (pin "1") (pinfunction "1_1") (pintype "passive"))
      (node (ref "U9") (pin "3") (pinfunction "EN_3") (pintype "passive"))
    )
    (net (code "50") (name "VDD") (class "Default")
      (node (ref "C1") (pin "2") (pinfunction "2_2") (pintype "passive"))
      (node (ref "C10") (pin "2") (pinfunction "2_2") (pintype "passive"))
      (node (ref "C3") (pin "2") (pinfunction "2_2") (pintype "passive"))
      (node (ref "C4") (pin "2") (pinfunction "2_2") (pintype "passive"))
      (node (ref "C6") (pin "2") (pinfunction "2_2") (pintype "passive"))
      (node (ref "C8") (pin "2") (pinfunction "2_2") (pintype "passive"))
      (node (ref "CB1") (pin "2") (pinfunction "2_2") (pintype "passive"))
      (node (ref "P1") (pin "1") (pinfunction "1_1") (pintype "passive"))
      (node (ref "R1") (pin "2") (pinfunction "2_2") (pintype "passive"))
      (node (ref "R3") (pin "2") (pinfunction "2_2") (pintype "passive"))
      (node (ref "R7") (pin "2") (pinfunction "2_2") (pintype "passive"))
      (node (ref "R8") (pin "2") (pinfunction "2_2") (pintype "passive"))
      (node (ref "SW1") (pin "1") (pinfunction "1_1") (pintype "passive"))
      (node (ref "U1") (pin "7") (pinfunction "SLEEP_N_7") (pintype "input"))
      (node (ref "U1") (pin "8") (pinfunction "VCC_8") (pintype "power_in"))
      (node (ref "U2") (pin "10") (pinfunction "VDD_10") (pintype "power_in"))
      (node (ref "U3") (pin "12") (pinfunction "CSB_12") (pintype "input"))
      (node (ref "U3") (pin "5") (pinfunction "VDDIO_5") (pintype "power_in"))
      (node (ref "U3") (pin "8") (pinfunction "VDD_8") (pintype "power_in"))
      (node (ref "U4") (pin "7") (pinfunction "SLEEP_N_7") (pintype "input"))
      (node (ref "U4") (pin "8") (pinfunction "VCC_8") (pintype "power_in"))
      (node (ref "U5") (pin "C1") (pinfunction "VDD_C1") (pintype "power_in"))
      (node (ref "U6") (pin "7") (pinfunction "SLEEP_N_7") (pintype "input"))
      (node (ref "U6") (pin "8") (pinfunction "VCC_8") (pintype "power_in"))
      (node (ref "U7") (pin "7") (pinfunction "SLEEP_N_7") (pintype "input"))
      (node (ref "U7") (pin "8") (pinfunction "VCC_8") (pintype "power_in"))
      (node (ref "U9") (pin "1") (pinfunction "OUT_1") (pintype "power_in"))
    )
    (net (code "51") (name "unconnected-(J1-D+-Pad3)") (class "Default")
      (node (ref "J1") (pin "3") (pinfunction "D+_3") (pintype "passive"))
    )
    (net (code "52") (name "unconnected-(J1-D--Pad2)") (class "Default")
      (node (ref "J1") (pin "2") (pinfunction "D-_2") (pintype "passive"))
    )
    (net (code "53") (name "unconnected-(J1-ID-Pad4)") (class "Default")
      (node (ref "J1") (pin "4") (pinfunction "ID_4") (pintype "passive"))
    )
    (net (code "54") (name "unconnected-(J1-SHLD2-Pad7)") (class "Default")
      (node (ref "J1") (pin "7") (pinfunction "SHLD2_7") (pintype "passive"))
    )
    (net (code "55") (name "unconnected-(J1-SHLD3-Pad8)") (class "Default")
      (node (ref "J1") (pin "8") (pinfunction "SHLD3_8") (pintype "passive"))
    )
    (net (code "56") (name "unconnected-(J1-SHLD4-Pad9)") (class "Default")
      (node (ref "J1") (pin "9") (pinfunction "SHLD4_9") (pintype "passive"))
    )
    (net (code "57") (name "unconnected-(LS1-PadN2)") (class "Default")
      (node (ref "LS1") (pin "N2") (pinfunction "N2_N2") (pintype "passive"))
    )
    (net (code "58") (name "unconnected-(LS1-PadP2)") (class "Default")
      (node (ref "LS1") (pin "P2") (pinfunction "P2_P2") (pintype "passive"))
    )
    (net (code "59") (name "unconnected-(LS2-PadN2)") (class "Default")
      (node (ref "LS2") (pin "N2") (pinfunction "N2_N2") (pintype "passive"))
    )
    (net (code "60") (name "unconnected-(LS2-PadP2)") (class "Default")
      (node (ref "LS2") (pin "P2") (pinfunction "P2_P2") (pintype "passive"))
    )
    (net (code "61") (name "unconnected-(LS3-PadN2)") (class "Default")
      (node (ref "LS3") (pin "N2") (pinfunction "N2_N2") (pintype "passive"))
    )
    (net (code "62") (name "unconnected-(LS3-PadP2)") (class "Default")
      (node (ref "LS3") (pin "P2") (pinfunction "P2_P2") (pintype "passive"))
    )
    (net (code "63") (name "unconnected-(P1-Pad6)") (class "Default")
      (node (ref "P1") (pin "6") (pinfunction "6_6") (pintype "passive+no_connect"))
    )
    (net (code "64") (name "unconnected-(P1-Pad7)") (class "Default")
      (node (ref "P1") (pin "7") (pinfunction "7_7") (pintype "passive"))
    )
    (net (code "65") (name "unconnected-(P1-Pad8)") (class "Default")
      (node (ref "P1") (pin "8") (pinfunction "8_8") (pintype "passive"))
    )
    (net (code "66") (name "unconnected-(SW2-Pad3)") (class "Default")
      (node (ref "SW2") (pin "3") (pinfunction "3_3") (pintype "passive"))
    )
    (net (code "67") (name "unconnected-(U1-PAD-Pad9)") (class "Default")
      (node (ref "U1") (pin "9") (pinfunction "PAD_9") (pintype "power_in"))
    )
    (net (code "68") (name "unconnected-(U3-ASCX-Pad3)") (class "Default")
      (node (ref "U3") (pin "3") (pinfunction "ASCX_3") (pintype "bidirectional"))
    )
    (net (code "69") (name "unconnected-(U3-ASDX-Pad2)") (class "Default")
      (node (ref "U3") (pin "2") (pinfunction "ASDX_2") (pintype "bidirectional"))
    )
    (net (code "70") (name "unconnected-(U3-INT1-Pad4)") (class "Default")
      (node (ref "U3") (pin "4") (pinfunction "INT1_4") (pintype "bidirectional+no_connect"))
    )
    (net (code "71") (name "unconnected-(U3-INT2-Pad9)") (class "Default")
      (node (ref "U3") (pin "9") (pinfunction "INT2_9") (pintype "bidirectional+no_connect"))
    )
    (net (code "72") (name "unconnected-(U3-OSCB-Pad10)") (class "Default")
      (node (ref "U3") (pin "10") (pinfunction "OSCB_10") (pintype "input+no_connect"))
    )
    (net (code "73") (name "unconnected-(U3-OSDO-Pad11)") (class "Default")
      (node (ref "U3") (pin "11") (pinfunction "OSDO_11") (pintype "output"))
    )
    (net (code "74") (name "unconnected-(U4-PAD-Pad9)") (class "Default")
      (node (ref "U4") (pin "9") (pinfunction "PAD_9") (pintype "power_in"))
    )
    (net (code "75") (name "unconnected-(U5-D+-PadA4)") (class "Default")
      (node (ref "U5") (pin "A4") (pinfunction "D+_A4") (pintype "power_in"))
    )
    (net (code "76") (name "unconnected-(U5-D--PadA5)") (class "Default")
      (node (ref "U5") (pin "A5") (pinfunction "D-_A5") (pintype "power_in"))
    )
    (net (code "77") (name "unconnected-(U5-DCCH-PadA7)") (class "Default")
      (node (ref "U5") (pin "A7") (pinfunction "DCCH_A7") (pintype "power_in"))
    )
    (net (code "78") (name "unconnected-(U5-P0.02{slash}NFC1-PadA8)") (class "Default")
      (node (ref "U5") (pin "A8") (pinfunction "P0.02/NFC1_A8") (pintype "bidirectional"))
    )
    (net (code "79") (name "unconnected-(U5-P0.03{slash}NFC2-PadA9)") (class "Default")
      (node (ref "U5") (pin "A9") (pinfunction "P0.03/NFC2_A9") (pintype "bidirectional"))
    )
    (net (code "80") (name "unconnected-(U5-P0.06{slash}AIN2-PadB3)") (class "Default")
      (node (ref "U5") (pin "B3") (pinfunction "P0.06/AIN2_B3") (pintype "bidirectional"))
    )
    (net (code "81") (name "unconnected-(U5-P0.07{slash}AIN3-PadB6)") (class "Default")
      (node (ref "U5") (pin "B6") (pinfunction "P0.07/AIN3_B6") (pintype "bidirectional"))
    )
    (net (code "82") (name "unconnected-(U5-P0.08{slash}TD3-PadB9)") (class "Default")
      (node (ref "U5") (pin "B9") (pinfunction "P0.08/TD3_B9") (pintype "bidirectional"))
    )
    (net (code "83") (name "unconnected-(U5-P0.09{slash}TD2-PadC7)") (class "Default")
      (node (ref "U5") (pin "C7") (pinfunction "P0.09/TD2_C7") (pintype "bidirectional"))
    )
    (net (code "84") (name "unconnected-(U5-P0.10{slash}TD1-PadA10)") (class "Default")
      (node (ref "U5") (pin "A10") (pinfunction "P0.10/TD1_A10") (pintype "bidirectional"))
    )
    (net (code "85") (name "unconnected-(U5-P0.11{slash}TDO-PadC8)") (class "Default")
      (node (ref "U5") (pin "C8") (pinfunction "P0.11/TDO_C8") (pintype "bidirectional"))
    )
    (net (code "86") (name "unconnected-(U5-P0.12{slash}TC-PadD2)") (class "Default")
      (node (ref "U5") (pin "D2") (pinfunction "P0.12/TC_D2") (pintype "bidirectional"))
    )
    (net (code "87") (name "unconnected-(U5-P0.13{slash}QSPI0-PadC2)") (class "Default")
      (node (ref "U5") (pin "C2") (pinfunction "P0.13/QSPI0_C2") (pintype "bidirectional"))
    )
    (net (code "88") (name "unconnected-(U5-P0.14{slash}QSPI1-PadC5)") (class "Default")
      (node (ref "U5") (pin "C5") (pinfunction "P0.14/QSPI1_C5") (pintype "bidirectional"))
    )
    (net (code "89") (name "unconnected-(U5-P0.15{slash}QSPI2-PadC4)") (class "Default")
      (node (ref "U5") (pin "C4") (pinfunction "P0.15/QSPI2_C4") (pintype "bidirectional"))
    )
    (net (code "90") (name "unconnected-(U5-P0.16-PadC6)") (class "Default")
      (node (ref "U5") (pin "C6") (pinfunction "P0.16_C6") (pintype "bidirectional"))
    )
    (net (code "91") (name "unconnected-(U5-P0.17{slash}QSPI_CLK-PadC9)") (class "Default")
      (node (ref "U5") (pin "C9") (pinfunction "P0.17/QSPI_CLK_C9") (pintype "bidirectional"))
    )
    (net (code "92") (name "unconnected-(U5-P0.18{slash}QSPI_CS-PadD4)") (class "Default")
      (node (ref "U5") (pin "D4") (pinfunction "P0.18/QSPI_CS_D4") (pintype "bidirectional"))
    )
    (net (code "93") (name "unconnected-(U5-P0.24-PadD10)") (class "Default")
      (node (ref "U5") (pin "D10") (pinfunction "P0.24_D10") (pintype "bidirectional"))
    )
    (net (code "94") (name "unconnected-(U5-P0.25{slash}AIN4-PadF10)") (class "Default")
      (node (ref "U5") (pin "F10") (pinfunction "P0.25/AIN4_F10") (pintype "bidirectional"))
    )
    (net (code "95") (name "unconnected-(U5-P0.26{slash}AIN5-PadE10)") (class "Default")
      (node (ref "U5") (pin "E10") (pinfunction "P0.26/AIN5_E10") (pintype "bidirectional"))
    )
    (net (code "96") (name "unconnected-(U5-P0.27{slash}AIN6-PadE9)") (class "Default")
      (node (ref "U5") (pin "E9") (pinfunction "P0.27/AIN6_E9") (pintype "bidirectional"))
    )
    (net (code "97") (name "unconnected-(U5-P0.28{slash}AIN7-PadE6)") (class "Default")
      (node (ref "U5") (pin "E6") (pinfunction "P0.28/AIN7_E6") (pintype "bidirectional"))
    )
    (net (code "98") (name "unconnected-(U5-P0.29-PadE8)") (class "Default")
      (node (ref "U5") (pin "E8") (pinfunction "P0.29_E8") (pintype "bidirectional"))
    )
    (net (code "99") (name "unconnected-(U5-P0.30-PadE2)") (class "Default")
      (node (ref "U5") (pin "E2") (pinfunction "P0.30_E2") (pintype "bidirectional"))
    )
    (net (code "100") (name "unconnected-(U5-P0.31-PadE3)") (class "Default")
      (node (ref "U5") (pin "E3") (pinfunction "P0.31_E3") (pintype "bidirectional"))
    )
    (net (code "101") (name "unconnected-(U5-P1.00-PadB7)") (class "Default")
      (node (ref "U5") (pin "B7") (pinfunction "P1.00_B7") (pintype "bidirectional"))
    )
    (net (code "102") (name "unconnected-(U5-P1.01-PadB5)") (class "Default")
      (node (ref "U5") (pin "B5") (pinfunction "P1.01_B5") (pintype "bidirectional"))
    )
    (net (code "103") (name "unconnected-(U5-P1.04-PadD9)") (class "Default")
      (node (ref "U5") (pin "D9") (pinfunction "P1.04_D9") (pintype "bidirectional"))
    )
    (net (code "104") (name "unconnected-(U5-VBUS-PadA2)") (class "Default")
      (node (ref "U5") (pin "A2") (pinfunction "VBUS_A2") (pintype "power_in"))
    )
    (net (code "105") (name "unconnected-(U5-VDDH-PadA6)") (class "Default")
      (node (ref "U5") (pin "A6") (pinfunction "VDDH_A6") (pintype "power_in"))
    )
    (net (code "106") (name "unconnected-(U6-PAD-Pad9)") (class "Default")
      (node (ref "U6") (pin "9") (pinfunction "PAD_9") (pintype "power_in"))
    )
    (net (code "107") (name "unconnected-(U7-PAD-Pad9)") (class "Default")
      (node (ref "U7") (pin "9") (pinfunction "PAD_9") (pintype "power_in"))
    )
  )
)
